# slave_board_CHM.net
KiCad netlist of a schematic drawn in Altium Designer
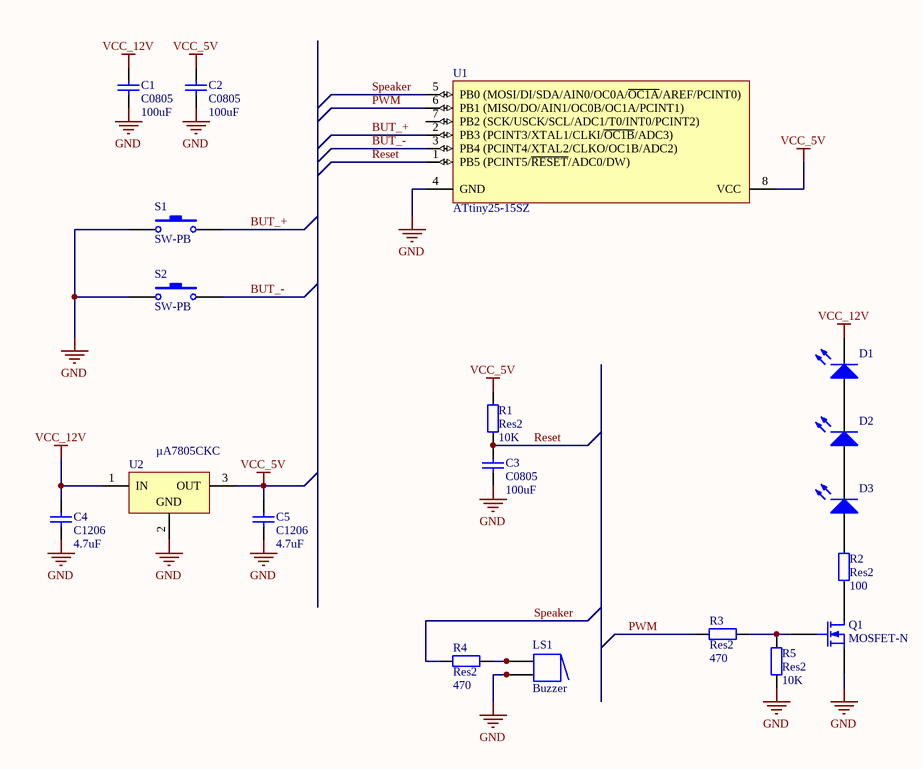
[diagram p0: slave board_CHM.SchDoc]

(export (version "E")
  (design (tool "Eeschema 10.0.6"))
  (components
    (comp (ref "C1")
      (value "C0805")
      (footprint "0805")
      (description "Ceramic Chip Capacitor - Standard")
      (fields (field (name "ALTIUM_VALUE") "100uF") (field (name "PUBLISHER") "Altium Limited"))
      (libsource (lib "KEMET Chip Capacitor") (part "C0805"))
    )
    (comp (ref "C2")
      (value "C0805")
      (footprint "0805")
      (description "Ceramic Chip Capacitor - Standard")
      (fields (field (name "ALTIUM_VALUE") "100uF") (field (name "PUBLISHER") "Altium Limited"))
      (libsource (lib "KEMET Chip Capacitor") (part "C0805"))
    )
    (comp (ref "C3")
      (value "C0805")
      (footprint "0805")
      (description "Ceramic Chip Capacitor - Standard")
      (fields (field (name "ALTIUM_VALUE") "100uF") (field (name "PUBLISHER") "Altium Limited"))
      (libsource (lib "KEMET Chip Capacitor") (part "C0805"))
    )
    (comp (ref "C4")
      (value "C1206")
      (footprint "1206")
      (description "Ceramic Chip Capacitor - Standard")
      (fields (field (name "ALTIUM_VALUE") "4.7uF") (field (name "PUBLISHER") "Altium Limited"))
      (libsource (lib "KEMET Chip Capacitor") (part "C1206"))
    )
    (comp (ref "C5")
      (value "C1206")
      (footprint "1206")
      (description "Ceramic Chip Capacitor - Standard")
      (fields (field (name "ALTIUM_VALUE") "4.7uF") (field (name "PUBLISHER") "Altium Limited"))
      (libsource (lib "KEMET Chip Capacitor") (part "C1206"))
    )
    (comp (ref "D1")
      (value "LED3")
      (footprint "3.5X2.8X1.9")
      (description "Typical BLUE SiC LED")
      (fields (field (name "PUBLISHER") "Altium Limited"))
      (libsource (lib "Miscellaneous Devices") (part "LED3"))
    )
    (comp (ref "D2")
      (value "LED3")
      (footprint "3.5X2.8X1.9")
      (description "Typical BLUE SiC LED")
      (fields (field (name "PUBLISHER") "Altium Limited"))
      (libsource (lib "Miscellaneous Devices") (part "LED3"))
    )
    (comp (ref "D3")
      (value "LED3")
      (footprint "3.5X2.8X1.9")
      (description "Typical BLUE SiC LED")
      (fields (field (name "PUBLISHER") "Altium Limited"))
      (libsource (lib "Miscellaneous Devices") (part "LED3"))
    )
    (comp (ref "LS1")
      (value "Buzzer")
      (footprint "ABSM-1574")
      (description "Magnetic Transducer Buzzer")
      (fields (field (name "PUBLISHER") "Altium Limited"))
      (libsource (lib "Miscellaneous Devices") (part "Buzzer"))
    )
    (comp (ref "Q1")
      (value "MOSFET-N")
      (footprint "E3")
      (description "N-Channel MOSFET")
      (fields (field (name "PUBLISHER") "Altium Limited"))
      (libsource (lib "Miscellaneous Devices") (part "MOSFET-N"))
    )
    (comp (ref "R1")
      (value "Res2")
      (footprint "6-0805_M")
      (description "Resistor")
      (fields (field (name "ALTIUM_VALUE") "10K") (field (name "PUBLISHER") "Altium Limited"))
      (libsource (lib "") (part "Res2_1"))
    )
    (comp (ref "R2")
      (value "Res2")
      (footprint "6-0805_M")
      (description "Resistor")
      (fields (field (name "ALTIUM_VALUE") "100") (field (name "PUBLISHER") "Altium Limited"))
      (libsource (lib "") (part "Res2_1"))
    )
    (comp (ref "R3")
      (value "Res2")
      (footprint "6-0805_M")
      (description "Resistor")
      (fields (field (name "ALTIUM_VALUE") "470") (field (name "PUBLISHER") "Altium Limited"))
      (libsource (lib "Miscellaneous Devices") (part "Res2"))
    )
    (comp (ref "R4")
      (value "Res2")
      (footprint "6-0805_M")
      (description "Resistor")
      (fields (field (name "ALTIUM_VALUE") "470") (field (name "PUBLISHER") "Altium Limited"))
      (libsource (lib "Miscellaneous Devices") (part "Res2"))
    )
    (comp (ref "R5")
      (value "Res2")
      (footprint "6-0805_M")
      (description "Resistor")
      (fields (field (name "ALTIUM_VALUE") "10K") (field (name "PUBLISHER") "Altium Limited"))
      (libsource (lib "") (part "Res2_1"))
    )
    (comp (ref "S1")
      (value "SW-PB")
      (footprint "SPST-2")
      (description "Switch")
      (fields (field (name "PUBLISHER") "Altium Limited"))
      (libsource (lib "Miscellaneous Devices") (part "SW-PB"))
    )
    (comp (ref "S2")
      (value "SW-PB")
      (footprint "SPST-2")
      (description "Switch")
      (fields (field (name "PUBLISHER") "Altium Limited"))
      (libsource (lib "Miscellaneous Devices") (part "SW-PB"))
    )
    (comp (ref "U1")
      (value "ATtiny25-15SZ")
      (footprint "T5_N")
      (fields (field (name "PUBLISHER") "Altium Limited"))
      (libsource (lib "Atmel Microcontroller 8-Bit Automotive AVR") (part "ATtiny25-15SZ"))
    )
    (comp (ref "U2")
      (value "µA7805CKC")
      (footprint "KC03")
      (description "Positive-Voltage Regulator")
      (fields (field (name "PUBLISHER") "Altium Limited"))
      (libsource (lib "TI Power Mgt Voltage Regulator") (part "µA7805CKC"))
    )
  )
  (nets
    (net (code "1") (name "/BUT_+") (class "Default")
      (node (ref "S1") (pin "2") (pinfunction "2_2") (pintype "passive"))
      (node (ref "U1") (pin "2") (pinfunction "PB3_(PCINT3/XTAL1/CLKI/~{OC1B}/ADC3)_2") (pintype "bidirectional"))
    )
    (net (code "2") (name "/BUT_-") (class "Default")
      (node (ref "S2") (pin "2") (pinfunction "2_2") (pintype "passive"))
      (node (ref "U1") (pin "3") (pinfunction "PB4_(PCINT4/XTAL2/CLKO/OC1B/ADC2)_3") (pintype "bidirectional"))
    )
    (net (code "3") (name "/PWM") (class "Default")
      (node (ref "R3") (pin "1") (pinfunction "1_1") (pintype "passive"))
      (node (ref "U1") (pin "6") (pinfunction "PB1_(MISO/DO/AIN1/OC0B/OC1A/PCINT1)_6") (pintype "bidirectional"))
    )
    (net (code "4") (name "/Reset") (class "Default")
      (node (ref "C3") (pin "2") (pinfunction "2_2") (pintype "passive"))
      (node (ref "R1") (pin "1") (pinfunction "1_1") (pintype "passive"))
      (node (ref "U1") (pin "1") (pinfunction "PB5_(PCINT5/~{RESET}/ADC0/DW)_1") (pintype "bidirectional"))
    )
    (net (code "5") (name "/Speaker") (class "Default")
      (node (ref "R4") (pin "1") (pinfunction "1_1") (pintype "passive"))
      (node (ref "U1") (pin "5") (pinfunction "PB0_(MOSI/DI/SDA/AIN0/OC0A/~{OC1A}/AREF/PCINT0)_5") (pintype "bidirectional"))
    )
    (net (code "6") (name "GND") (class "Default")
      (node (ref "C1") (pin "1") (pinfunction "1_1") (pintype "passive"))
      (node (ref "C2") (pin "1") (pinfunction "1_1") (pintype "passive"))
      (node (ref "C3") (pin "1") (pinfunction "1_1") (pintype "passive"))
      (node (ref "C4") (pin "1") (pinfunction "1_1") (pintype "passive"))
      (node (ref "C5") (pin "1") (pinfunction "1_1") (pintype "passive"))
      (node (ref "LS1") (pin "2") (pinfunction "2_2") (pintype "passive"))
      (node (ref "LS1") (pin "2A") (pinfunction "2A_2A") (pintype "passive"))
      (node (ref "Q1") (pin "3") (pinfunction "S_3") (pintype "passive"))
      (node (ref "R5") (pin "1") (pinfunction "1_1") (pintype "passive"))
      (node (ref "S1") (pin "1") (pinfunction "1_1") (pintype "passive"))
      (node (ref "S2") (pin "1") (pinfunction "1_1") (pintype "passive"))
      (node (ref "U1") (pin "4") (pinfunction "GND_4") (pintype "power_in"))
      (node (ref "U2") (pin "2") (pinfunction "GND_2") (pintype "power_in"))
    )
    (net (code "7") (name "Net-(D1-A)") (class "Default")
      (node (ref "D1") (pin "1") (pinfunction "A_1") (pintype "passive"))
      (node (ref "D2") (pin "2") (pinfunction "K_2") (pintype "passive"))
    )
    (net (code "8") (name "Net-(D2-A)") (class "Default")
      (node (ref "D2") (pin "1") (pinfunction "A_1") (pintype "passive"))
      (node (ref "D3") (pin "2") (pinfunction "K_2") (pintype "passive"))
    )
    (net (code "9") (name "Net-(D3-A)") (class "Default")
      (node (ref "D3") (pin "1") (pinfunction "A_1") (pintype "passive"))
      (node (ref "R2") (pin "2") (pinfunction "2_2") (pintype "passive"))
    )
    (net (code "10") (name "Net-(LS1-Pad1)") (class "Default")
      (node (ref "LS1") (pin "1") (pinfunction "1_1") (pintype "passive"))
      (node (ref "LS1") (pin "1A") (pinfunction "1A_1A") (pintype "passive"))
      (node (ref "R4") (pin "2") (pinfunction "2_2") (pintype "passive"))
    )
    (net (code "11") (name "Net-(Q1-D)") (class "Default")
      (node (ref "Q1") (pin "1") (pinfunction "D_1") (pintype "passive"))
      (node (ref "R2") (pin "1") (pinfunction "1_1") (pintype "passive"))
    )
    (net (code "12") (name "Net-(Q1-G)") (class "Default")
      (node (ref "Q1") (pin "2") (pinfunction "G_2") (pintype "passive"))
      (node (ref "R3") (pin "2") (pinfunction "2_2") (pintype "passive"))
      (node (ref "R5") (pin "2") (pinfunction "2_2") (pintype "passive"))
    )
    (net (code "13") (name "VCC_5V") (class "Default")
      (node (ref "C2") (pin "2") (pinfunction "2_2") (pintype "passive"))
      (node (ref "C5") (pin "2") (pinfunction "2_2") (pintype "passive"))
      (node (ref "R1") (pin "2") (pinfunction "2_2") (pintype "passive"))
      (node (ref "U1") (pin "8") (pinfunction "VCC_8") (pintype "power_in"))
      (node (ref "U2") (pin "3") (pinfunction "OUT_3") (pintype "power_in"))
    )
    (net (code "14") (name "VCC_12V") (class "Default")
      (node (ref "C1") (pin "2") (pinfunction "2_2") (pintype "passive"))
      (node (ref "C4") (pin "2") (pinfunction "2_2") (pintype "passive"))
      (node (ref "D1") (pin "2") (pinfunction "K_2") (pintype "passive"))
      (node (ref "U2") (pin "1") (pinfunction "IN_1") (pintype "power_in"))
    )
    (net (code "15") (name "unconnected-(U1-PB2_(SCK{slash}USCK{slash}SCL{slash}ADC1{slash}T0{slash}INT0{slash}PCINT2)-Pad7)") (class "Default")
      (node (ref "U1") (pin "7") (pinfunction "PB2_(SCK/USCK/SCL/ADC1/T0/INT0/PCINT2)_7") (pintype "bidirectional"))
    )
  )
)
